# ExtConn.net
KiCad netlist of a schematic drawn in Altium Designer
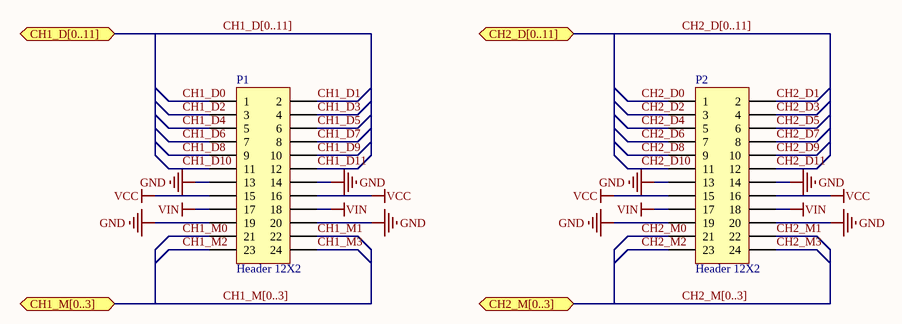
[diagram p0: ExtConn.SchDoc]

(export (version "E")
  (design (tool "Eeschema 10.0.6"))
  (components
    (comp (ref "P1")
      (value "Header 12X2")
      (footprint "HDR2X12")
      (description "Header, 12-Pin, Dual row")
      (fields (field (name "PUBLISHER") "Altium Limited"))
      (libsource (lib "Miscellaneous Connectors") (part "Header 12X2"))
    )
    (comp (ref "P2")
      (value "Header 12X2")
      (footprint "HDR2X12")
      (description "Header, 12-Pin, Dual row")
      (fields (field (name "PUBLISHER") "Altium Limited"))
      (libsource (lib "Miscellaneous Connectors") (part "Header 12X2"))
    )
  )
  (nets
    (net (code "1") (name "/CH1_D0") (class "Default")
      (node (ref "P1") (pin "1") (pinfunction "1_1") (pintype "passive"))
    )
    (net (code "2") (name "/CH1_D1") (class "Default")
      (node (ref "P1") (pin "2") (pinfunction "2_2") (pintype "passive"))
    )
    (net (code "3") (name "/CH1_D2") (class "Default")
      (node (ref "P1") (pin "3") (pinfunction "3_3") (pintype "passive"))
    )
    (net (code "4") (name "/CH1_D3") (class "Default")
      (node (ref "P1") (pin "4") (pinfunction "4_4") (pintype "passive"))
    )
    (net (code "5") (name "/CH1_D4") (class "Default")
      (node (ref "P1") (pin "5") (pinfunction "5_5") (pintype "passive"))
    )
    (net (code "6") (name "/CH1_D5") (class "Default")
      (node (ref "P1") (pin "6") (pinfunction "6_6") (pintype "passive"))
    )
    (net (code "7") (name "/CH1_D6") (class "Default")
      (node (ref "P1") (pin "7") (pinfunction "7_7") (pintype "passive"))
    )
    (net (code "8") (name "/CH1_D7") (class "Default")
      (node (ref "P1") (pin "8") (pinfunction "8_8") (pintype "passive"))
    )
    (net (code "9") (name "/CH1_D8") (class "Default")
      (node (ref "P1") (pin "9") (pinfunction "9_9") (pintype "passive"))
    )
    (net (code "10") (name "/CH1_D9") (class "Default")
      (node (ref "P1") (pin "10") (pinfunction "10_10") (pintype "passive"))
    )
    (net (code "11") (name "/CH1_D10") (class "Default")
      (node (ref "P1") (pin "11") (pinfunction "11_11") (pintype "passive"))
    )
    (net (code "12") (name "/CH1_D11") (class "Default")
      (node (ref "P1") (pin "12") (pinfunction "12_12") (pintype "passive"))
    )
    (net (code "14") (name "/CH1_M0") (class "Default")
      (node (ref "P1") (pin "21") (pinfunction "21_21") (pintype "passive"))
    )
    (net (code "15") (name "/CH1_M1") (class "Default")
      (node (ref "P1") (pin "22") (pinfunction "22_22") (pintype "passive"))
    )
    (net (code "16") (name "/CH1_M2") (class "Default")
      (node (ref "P1") (pin "23") (pinfunction "23_23") (pintype "passive"))
    )
    (net (code "17") (name "/CH1_M3") (class "Default")
      (node (ref "P1") (pin "24") (pinfunction "24_24") (pintype "passive"))
    )
    (net (code "19") (name "/CH2_D0") (class "Default")
      (node (ref "P2") (pin "1") (pinfunction "1_1") (pintype "passive"))
    )
    (net (code "20") (name "/CH2_D1") (class "Default")
      (node (ref "P2") (pin "2") (pinfunction "2_2") (pintype "passive"))
    )
    (net (code "21") (name "/CH2_D2") (class "Default")
      (node (ref "P2") (pin "3") (pinfunction "3_3") (pintype "passive"))
    )
    (net (code "22") (name "/CH2_D3") (class "Default")
      (node (ref "P2") (pin "4") (pinfunction "4_4") (pintype "passive"))
    )
    (net (code "23") (name "/CH2_D4") (class "Default")
      (node (ref "P2") (pin "5") (pinfunction "5_5") (pintype "passive"))
    )
    (net (code "24") (name "/CH2_D5") (class "Default")
      (node (ref "P2") (pin "6") (pinfunction "6_6") (pintype "passive"))
    )
    (net (code "25") (name "/CH2_D6") (class "Default")
      (node (ref "P2") (pin "7") (pinfunction "7_7") (pintype "passive"))
    )
    (net (code "26") (name "/CH2_D7") (class "Default")
      (node (ref "P2") (pin "8") (pinfunction "8_8") (pintype "passive"))
    )
    (net (code "27") (name "/CH2_D8") (class "Default")
      (node (ref "P2") (pin "9") (pinfunction "9_9") (pintype "passive"))
    )
    (net (code "28") (name "/CH2_D9") (class "Default")
      (node (ref "P2") (pin "10") (pinfunction "10_10") (pintype "passive"))
    )
    (net (code "29") (name "/CH2_D10") (class "Default")
      (node (ref "P2") (pin "11") (pinfunction "11_11") (pintype "passive"))
    )
    (net (code "30") (name "/CH2_D11") (class "Default")
      (node (ref "P2") (pin "12") (pinfunction "12_12") (pintype "passive"))
    )
    (net (code "32") (name "/CH2_M0") (class "Default")
      (node (ref "P2") (pin "21") (pinfunction "21_21") (pintype "passive"))
    )
    (net (code "33") (name "/CH2_M1") (class "Default")
      (node (ref "P2") (pin "22") (pinfunction "22_22") (pintype "passive"))
    )
    (net (code "34") (name "/CH2_M2") (class "Default")
      (node (ref "P2") (pin "23") (pinfunction "23_23") (pintype "passive"))
    )
    (net (code "35") (name "/CH2_M3") (class "Default")
      (node (ref "P2") (pin "24") (pinfunction "24_24") (pintype "passive"))
    )
    (net (code "37") (name "GND") (class "Default")
      (node (ref "P1") (pin "13") (pinfunction "13_13") (pintype "passive"))
      (node (ref "P1") (pin "14") (pinfunction "14_14") (pintype "passive"))
      (node (ref "P1") (pin "19") (pinfunction "19_19") (pintype "passive"))
      (node (ref "P1") (pin "20") (pinfunction "20_20") (pintype "passive"))
      (node (ref "P2") (pin "13") (pinfunction "13_13") (pintype "passive"))
      (node (ref "P2") (pin "14") (pinfunction "14_14") (pintype "passive"))
      (node (ref "P2") (pin "19") (pinfunction "19_19") (pintype "passive"))
      (node (ref "P2") (pin "20") (pinfunction "20_20") (pintype "passive"))
    )
    (net (code "38") (name "VCC") (class "Default")
      (node (ref "P1") (pin "15") (pinfunction "15_15") (pintype "passive"))
      (node (ref "P1") (pin "16") (pinfunction "16_16") (pintype "passive"))
      (node (ref "P2") (pin "15") (pinfunction "15_15") (pintype "passive"))
      (node (ref "P2") (pin "16") (pinfunction "16_16") (pintype "passive"))
    )
    (net (code "39") (name "VIN") (class "Default")
      (node (ref "P1") (pin "17") (pinfunction "17_17") (pintype "passive"))
      (node (ref "P1") (pin "18") (pinfunction "18_18") (pintype "passive"))
      (node (ref "P2") (pin "17") (pinfunction "17_17") (pintype "passive"))
      (node (ref "P2") (pin "18") (pinfunction "18_18") (pintype "passive"))
    )
  )
)
